# VREG.net
KiCad netlist of a schematic drawn in Altium Designer
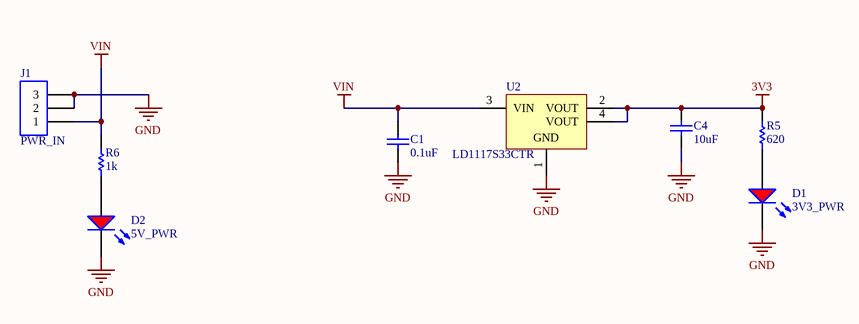
[diagram p0: VREG.SchDoc]

(export (version "E")
  (design (tool "Eeschema 10.0.6"))
  (components
    (comp (ref "C1")
      (value "0.1uF")
      (footprint "PCB-5bhg8adqnzhgtf4b63gj-1")
      (description "0402 0.1 uF 25 V ±10% Tolerance X5R SMT Multilayer Ceramic Capacitor")
      (fields (field (name "MANUFACTURER PART NUMBER") "TMK105BJ104KV-F"))
      (libsource (lib "CommunityVault") (part "SYM-76b0bfb95be4a977-1"))
    )
    (comp (ref "C4")
      (value "10uF")
      (footprint "PCB-19299738-1")
      (description "CAP CER 10UF 10V 10% X5R 0805")
      (fields (field (name "MANUFACTURER PART NUMBER") "GRM21BR61A106KE19L"))
      (libsource (lib "CommunityVault") (part "SYM-19299738-1"))
    )
    (comp (ref "D1")
      (value "3V3_PWR")
      (footprint "KING-LED0603-25-RED_V")
      (description "1.6 x 0.8 x 0.4 mm (0603) Red 120º Min 11.5mcd Max 28.5mcd SMT LED")
      (fields (field (name "MANUFACTURER PART NUMBER") "19-217/R6C-AL1M2VY/3T"))
      (libsource (lib "CommunityVault") (part "LED_RED_AC"))
    )
    (comp (ref "D2")
      (value "5V_PWR")
      (footprint "KING-LED0603-25-RED_V")
      (description "1.6 x 0.8 x 0.4 mm (0603) Red 120º Min 11.5mcd Max 28.5mcd SMT LED")
      (fields (field (name "MANUFACTURER PART NUMBER") "19-217/R6C-AL1M2VY/3T"))
      (libsource (lib "CommunityVault") (part "LED_RED_AC"))
    )
    (comp (ref "J1")
      (value "PWR_IN")
      (footprint "ADAM-ADC-002-3_V")
      (description "DC Power Connectors DC POWER JACK 2.5MM PIN TYPE 002")
      (fields (field (name "MANUFACTURER PART NUMBER") "ADC-002-2"))
      (libsource (lib "CommunityVault") (part "ADAM-ADC-002-3"))
    )
    (comp (ref "R5")
      (value "620")
      (footprint "RESC1005X40X25NL05T05")
      (description "Thick Film Resistors - SMD 0402 620ohms 5% Tol")
      (fields (field (name "MANUFACTURER PART NUMBER") "ERJ-2GEJ621X"))
      (libsource (lib "CommunityVault") (part "RES-2"))
    )
    (comp (ref "R6")
      (value "1k")
      (footprint "RESC1005X40X25NL05T05")
      (description "RES SMD 1K OHM 5% 1/16W 0402")
      (fields (field (name "MANUFACTURER PART NUMBER") "CRCW04021K00JNTD"))
      (libsource (lib "CommunityVault") (part "RES-2"))
    )
    (comp (ref "U2")
      (value "LD1117S33CTR")
      (footprint "SOT-223_N")
      (description "Fixed Low Drop Positive Voltage Regulator, 3.3V, 4-Pin SOT-223, Tape and Reel")
      (libsource (lib "CommunityVault") (part "PM-REG-LD1117-SOT4"))
    )
  )
  (nets
    (net (code "1") (name "3V3") (class "Default")
      (node (ref "C4") (pin "2") (pinfunction "2_2") (pintype "passive"))
      (node (ref "R5") (pin "2") (pinfunction "2_2") (pintype "passive"))
      (node (ref "U2") (pin "2") (pinfunction "VOUT_2") (pintype "power_in"))
      (node (ref "U2") (pin "4") (pinfunction "VOUT_4") (pintype "power_in"))
    )
    (net (code "2") (name "GND") (class "Default")
      (node (ref "C1") (pin "1") (pinfunction "1_1") (pintype "passive"))
      (node (ref "C4") (pin "1") (pinfunction "1_1") (pintype "passive"))
      (node (ref "D1") (pin "2") (pinfunction "C_2") (pintype "passive"))
      (node (ref "D2") (pin "2") (pinfunction "C_2") (pintype "passive"))
      (node (ref "J1") (pin "2") (pinfunction "2_2") (pintype "passive"))
      (node (ref "J1") (pin "3") (pinfunction "3_3") (pintype "passive"))
      (node (ref "U2") (pin "1") (pinfunction "GND_1") (pintype "power_in"))
    )
    (net (code "3") (name "Net-(D1-A)") (class "Default")
      (node (ref "D1") (pin "1") (pinfunction "A_1") (pintype "passive"))
      (node (ref "R5") (pin "1") (pinfunction "1_1") (pintype "passive"))
    )
    (net (code "4") (name "Net-(D2-A)") (class "Default")
      (node (ref "D2") (pin "1") (pinfunction "A_1") (pintype "passive"))
      (node (ref "R6") (pin "1") (pinfunction "1_1") (pintype "passive"))
    )
    (net (code "5") (name "VIN") (class "Default")
      (node (ref "C1") (pin "2") (pinfunction "2_2") (pintype "passive"))
      (node (ref "J1") (pin "1") (pinfunction "1_1") (pintype "passive"))
      (node (ref "R6") (pin "2") (pinfunction "2_2") (pintype "passive"))
      (node (ref "U2") (pin "3") (pinfunction "VIN_3") (pintype "power_in"))
    )
  )
)
